# WeatherStation.net
KiCad netlist of a schematic drawn in EAGLE
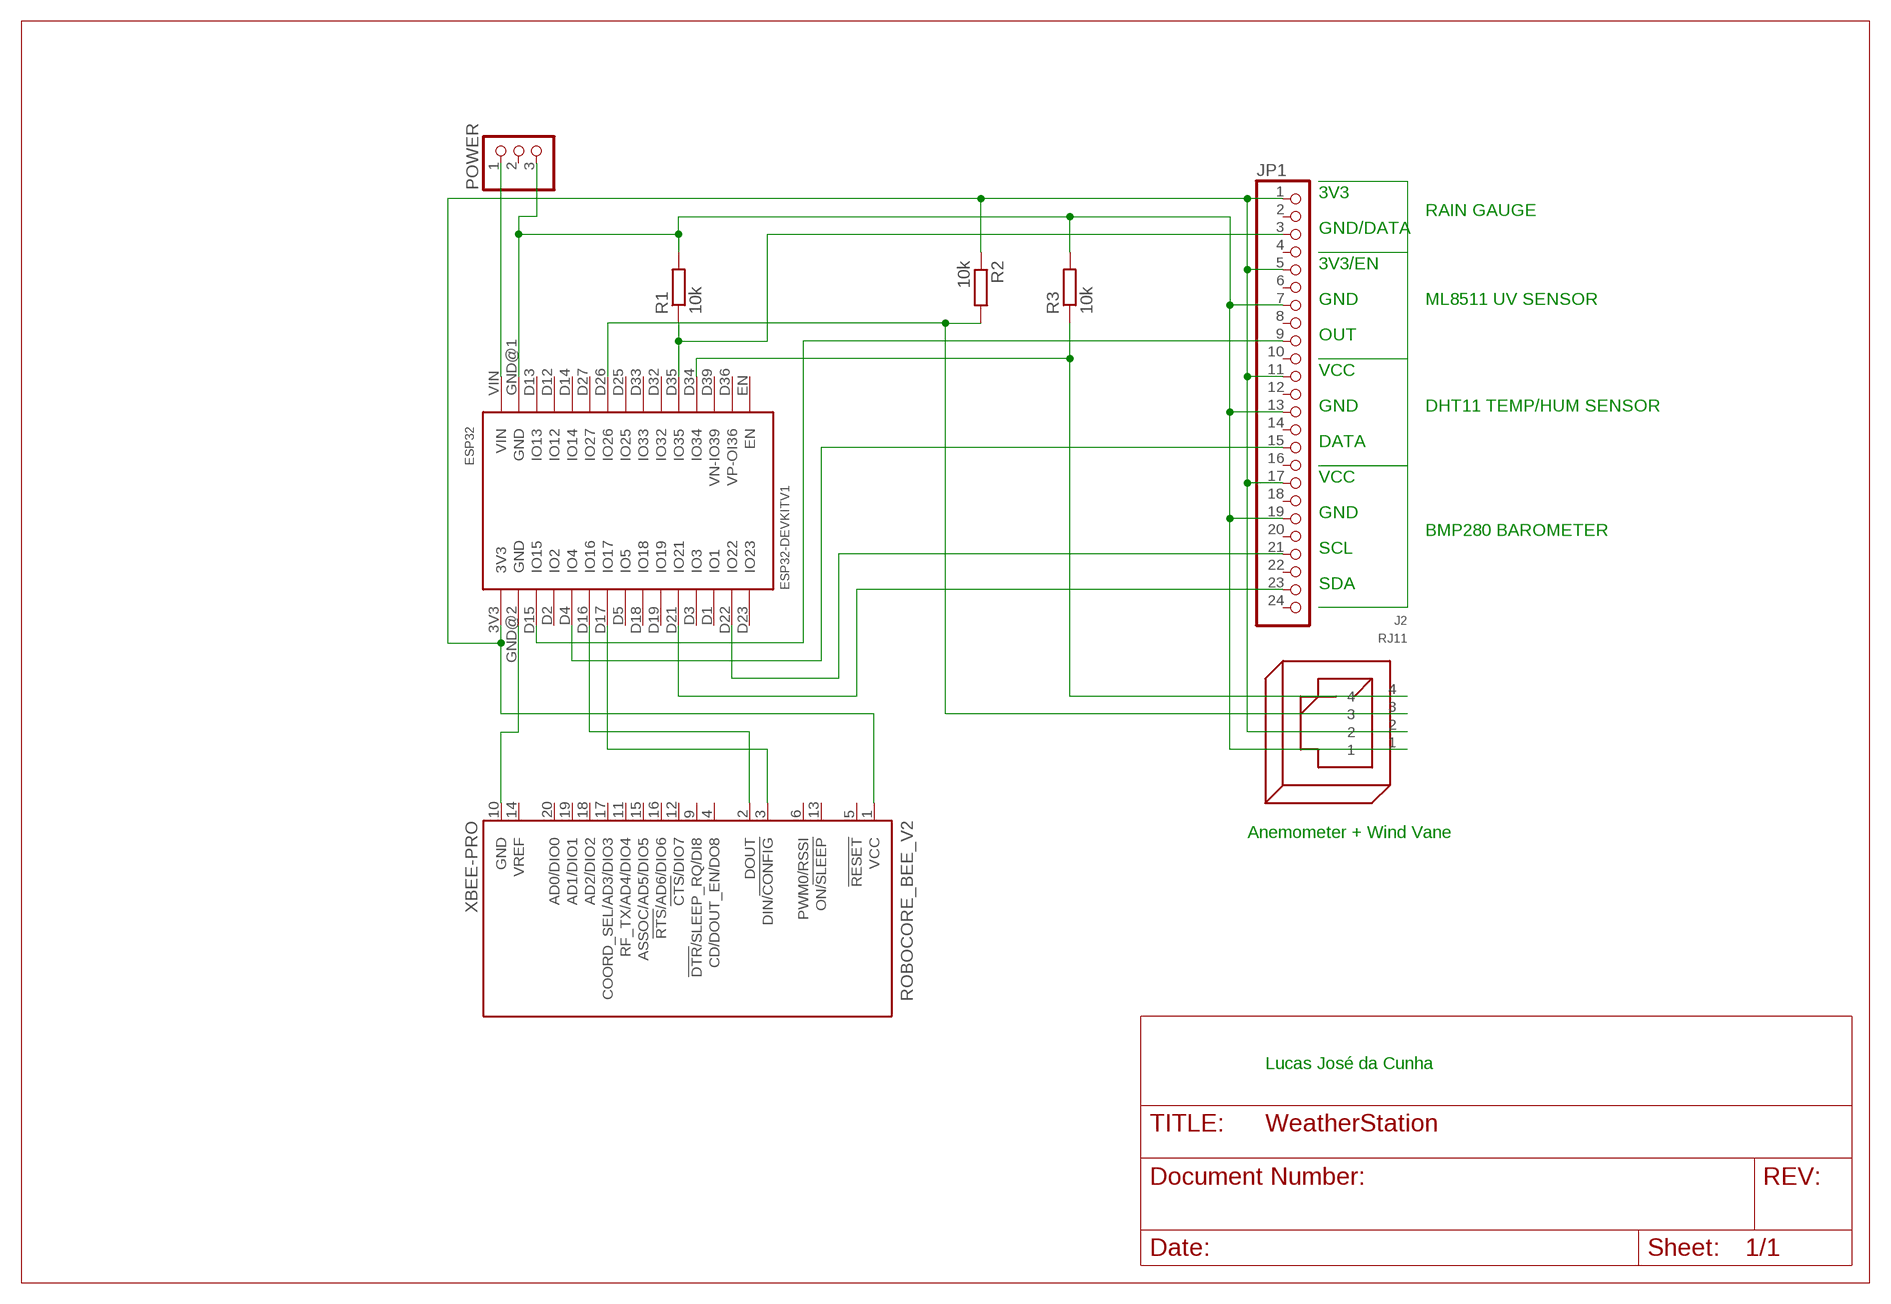
[diagram p0: schematic, sheet 1]

(export (version "E")
  (design (tool "Eeschema 10.0.6"))
  (components
    (comp (ref "ESP32")
      (value "ESP32DEVKITV1")
      (footprint "eagle-import:ESP32-DEVKITV1")
      (libsource (lib "eagle-import") (part "ESP32DEVKITV1"))
    )
    (comp (ref "J2")
      (value "RJ11")
      (footprint "eagle-import:RJ11")
      (libsource (lib "eagle-import") (part "RJ11"))
    )
    (comp (ref "JP1")
      (value "PINHD-1X24")
      (footprint "eagle-import:1X24")
      (libsource (lib "eagle-import") (part "PINHD-1X24"))
    )
    (comp (ref "POWER")
      (value "PINHD-1X3")
      (footprint "eagle-import:1X03")
      (libsource (lib "eagle-import") (part "PINHD-1X3"))
    )
    (comp (ref "R1")
      (value "10k")
      (footprint "eagle-import:0204_7")
      (libsource (lib "eagle-import") (part "R-EU_0204/7"))
    )
    (comp (ref "R2")
      (value "10k")
      (footprint "eagle-import:0204_7")
      (libsource (lib "eagle-import") (part "R-EU_0204/7"))
    )
    (comp (ref "R3")
      (value "10k")
      (footprint "eagle-import:0204_7")
      (libsource (lib "eagle-import") (part "R-EU_0204/7"))
    )
    (comp (ref "ROBOCORE_BEE_V2")
      (value "XBEE-PRO")
      (footprint "eagle-import:XBEE-PRO")
      (fields (field (name "MPN") "XBP24-AWI-001"))
      (libsource (lib "eagle-import") (part "XBEE-PRO"))
    )
  )
  (nets
    (net (code "1") (name "Net-(ESP32-GND-PadGND@1)") (class "Default")
      (node (ref "ESP32") (pin "GND@1") (pinfunction "GND_GND@1") (pintype "bidirectional"))
      (node (ref "J2") (pin "1") (pinfunction "1_1") (pintype "bidirectional"))
      (node (ref "JP1") (pin "13") (pinfunction "13_13") (pintype "passive"))
      (node (ref "JP1") (pin "19") (pinfunction "19_19") (pintype "passive"))
      (node (ref "JP1") (pin "7") (pinfunction "7_7") (pintype "passive"))
      (node (ref "POWER") (pin "3") (pinfunction "3_3") (pintype "passive"))
      (node (ref "R1") (pin "2") (pinfunction "2_2") (pintype "passive"))
      (node (ref "R3") (pin "2") (pinfunction "2_2") (pintype "passive"))
    )
    (net (code "2") (name "Net-(ESP32-IO4)") (class "Default")
      (node (ref "ESP32") (pin "D4") (pinfunction "IO4_D4") (pintype "bidirectional"))
      (node (ref "JP1") (pin "15") (pinfunction "15_15") (pintype "passive"))
    )
    (net (code "3") (name "Net-(ESP32-IO15)") (class "Default")
      (node (ref "ESP32") (pin "D15") (pinfunction "IO15_D15") (pintype "bidirectional"))
      (node (ref "JP1") (pin "9") (pinfunction "9_9") (pintype "passive"))
    )
    (net (code "4") (name "Net-(ESP32-IO16)") (class "Default")
      (node (ref "ESP32") (pin "D16") (pinfunction "IO16_D16") (pintype "bidirectional"))
      (node (ref "ROBOCORE_BEE_V2") (pin "2") (pinfunction "DOUT_2") (pintype "output"))
    )
    (net (code "5") (name "Net-(ESP32-IO17)") (class "Default")
      (node (ref "ESP32") (pin "D17") (pinfunction "IO17_D17") (pintype "bidirectional"))
      (node (ref "ROBOCORE_BEE_V2") (pin "3") (pinfunction "DIN/~{CONFIG}_3") (pintype "input"))
    )
    (net (code "6") (name "Net-(ESP32-IO21)") (class "Default")
      (node (ref "ESP32") (pin "D21") (pinfunction "IO21_D21") (pintype "bidirectional"))
      (node (ref "JP1") (pin "23") (pinfunction "23_23") (pintype "passive"))
    )
    (net (code "7") (name "Net-(ESP32-IO22)") (class "Default")
      (node (ref "ESP32") (pin "D22") (pinfunction "IO22_D22") (pintype "bidirectional"))
      (node (ref "JP1") (pin "21") (pinfunction "21_21") (pintype "passive"))
    )
    (net (code "8") (name "Net-(ESP32-IO26)") (class "Default")
      (node (ref "ESP32") (pin "D26") (pinfunction "IO26_D26") (pintype "bidirectional"))
      (node (ref "J2") (pin "3") (pinfunction "3_3") (pintype "bidirectional"))
      (node (ref "R2") (pin "2") (pinfunction "2_2") (pintype "passive"))
    )
    (net (code "9") (name "Net-(ESP32-IO34)") (class "Default")
      (node (ref "ESP32") (pin "D34") (pinfunction "IO34_D34") (pintype "bidirectional"))
      (node (ref "J2") (pin "4") (pinfunction "4_4") (pintype "bidirectional"))
      (node (ref "R3") (pin "1") (pinfunction "1_1") (pintype "passive"))
    )
    (net (code "10") (name "Net-(ESP32-IO35)") (class "Default")
      (node (ref "ESP32") (pin "D35") (pinfunction "IO35_D35") (pintype "bidirectional"))
      (node (ref "JP1") (pin "3") (pinfunction "3_3") (pintype "passive"))
      (node (ref "R1") (pin "1") (pinfunction "1_1") (pintype "passive"))
    )
    (net (code "11") (name "Net-(ESP32-PadVIN)") (class "Default")
      (node (ref "ESP32") (pin "VIN") (pinfunction "VIN_VIN") (pintype "bidirectional"))
      (node (ref "POWER") (pin "1") (pinfunction "1_1") (pintype "passive"))
    )
    (net (code "12") (name "Net-(ROBOCORE_BEE_V2-GND)") (class "Default")
      (node (ref "ESP32") (pin "GND@2") (pinfunction "GND_GND@2") (pintype "bidirectional"))
      (node (ref "ROBOCORE_BEE_V2") (pin "10") (pinfunction "GND_10") (pintype "power_in"))
    )
    (net (code "13") (name "Net-(ROBOCORE_BEE_V2-VCC)") (class "Default")
      (node (ref "ESP32") (pin "3V3") (pinfunction "3V3_3V3") (pintype "bidirectional"))
      (node (ref "J2") (pin "2") (pinfunction "2_2") (pintype "bidirectional"))
      (node (ref "JP1") (pin "1") (pinfunction "1_1") (pintype "passive"))
      (node (ref "JP1") (pin "11") (pinfunction "11_11") (pintype "passive"))
      (node (ref "JP1") (pin "17") (pinfunction "17_17") (pintype "passive"))
      (node (ref "JP1") (pin "5") (pinfunction "5_5") (pintype "passive"))
      (node (ref "R2") (pin "1") (pinfunction "1_1") (pintype "passive"))
      (node (ref "ROBOCORE_BEE_V2") (pin "1") (pinfunction "VCC_1") (pintype "power_in"))
    )
    (net (code "14") (name "unconnected-(ESP32-IO1-PadD1)") (class "Default")
      (node (ref "ESP32") (pin "D1") (pinfunction "IO1_D1") (pintype "bidirectional"))
    )
    (net (code "15") (name "unconnected-(ESP32-IO2-PadD2)") (class "Default")
      (node (ref "ESP32") (pin "D2") (pinfunction "IO2_D2") (pintype "bidirectional"))
    )
    (net (code "16") (name "unconnected-(ESP32-IO3-PadD3)") (class "Default")
      (node (ref "ESP32") (pin "D3") (pinfunction "IO3_D3") (pintype "bidirectional"))
    )
    (net (code "17") (name "unconnected-(ESP32-IO5-PadD5)") (class "Default")
      (node (ref "ESP32") (pin "D5") (pinfunction "IO5_D5") (pintype "bidirectional"))
    )
    (net (code "18") (name "unconnected-(ESP32-IO12-PadD12)") (class "Default")
      (node (ref "ESP32") (pin "D12") (pinfunction "IO12_D12") (pintype "bidirectional"))
    )
    (net (code "19") (name "unconnected-(ESP32-IO13-PadD13)") (class "Default")
      (node (ref "ESP32") (pin "D13") (pinfunction "IO13_D13") (pintype "bidirectional"))
    )
    (net (code "20") (name "unconnected-(ESP32-IO14-PadD14)") (class "Default")
      (node (ref "ESP32") (pin "D14") (pinfunction "IO14_D14") (pintype "bidirectional"))
    )
    (net (code "21") (name "unconnected-(ESP32-IO18-PadD18)") (class "Default")
      (node (ref "ESP32") (pin "D18") (pinfunction "IO18_D18") (pintype "bidirectional"))
    )
    (net (code "22") (name "unconnected-(ESP32-IO19-PadD19)") (class "Default")
      (node (ref "ESP32") (pin "D19") (pinfunction "IO19_D19") (pintype "bidirectional"))
    )
    (net (code "23") (name "unconnected-(ESP32-IO23-PadD23)") (class "Default")
      (node (ref "ESP32") (pin "D23") (pinfunction "IO23_D23") (pintype "bidirectional"))
    )
    (net (code "24") (name "unconnected-(ESP32-IO25-PadD25)") (class "Default")
      (node (ref "ESP32") (pin "D25") (pinfunction "IO25_D25") (pintype "bidirectional"))
    )
    (net (code "25") (name "unconnected-(ESP32-IO27-PadD27)") (class "Default")
      (node (ref "ESP32") (pin "D27") (pinfunction "IO27_D27") (pintype "bidirectional"))
    )
    (net (code "26") (name "unconnected-(ESP32-IO32-PadD32)") (class "Default")
      (node (ref "ESP32") (pin "D32") (pinfunction "IO32_D32") (pintype "bidirectional"))
    )
    (net (code "27") (name "unconnected-(ESP32-IO33-PadD33)") (class "Default")
      (node (ref "ESP32") (pin "D33") (pinfunction "IO33_D33") (pintype "bidirectional"))
    )
    (net (code "28") (name "unconnected-(ESP32-PadEN)") (class "Default")
      (node (ref "ESP32") (pin "EN") (pinfunction "EN_EN") (pintype "bidirectional"))
    )
    (net (code "29") (name "unconnected-(ESP32-VN-IO39-PadD39)") (class "Default")
      (node (ref "ESP32") (pin "D39") (pinfunction "VN-IO39_D39") (pintype "bidirectional"))
    )
    (net (code "30") (name "unconnected-(ESP32-VP-OI36-PadD36)") (class "Default")
      (node (ref "ESP32") (pin "D36") (pinfunction "VP-OI36_D36") (pintype "bidirectional"))
    )
    (net (code "31") (name "unconnected-(JP1-Pad2)") (class "Default")
      (node (ref "JP1") (pin "2") (pinfunction "2_2") (pintype "passive"))
    )
    (net (code "32") (name "unconnected-(JP1-Pad4)") (class "Default")
      (node (ref "JP1") (pin "4") (pinfunction "4_4") (pintype "passive"))
    )
    (net (code "33") (name "unconnected-(JP1-Pad6)") (class "Default")
      (node (ref "JP1") (pin "6") (pinfunction "6_6") (pintype "passive"))
    )
    (net (code "34") (name "unconnected-(JP1-Pad8)") (class "Default")
      (node (ref "JP1") (pin "8") (pinfunction "8_8") (pintype "passive"))
    )
    (net (code "35") (name "unconnected-(JP1-Pad10)") (class "Default")
      (node (ref "JP1") (pin "10") (pinfunction "10_10") (pintype "passive"))
    )
    (net (code "36") (name "unconnected-(JP1-Pad12)") (class "Default")
      (node (ref "JP1") (pin "12") (pinfunction "12_12") (pintype "passive"))
    )
    (net (code "37") (name "unconnected-(JP1-Pad14)") (class "Default")
      (node (ref "JP1") (pin "14") (pinfunction "14_14") (pintype "passive"))
    )
    (net (code "38") (name "unconnected-(JP1-Pad16)") (class "Default")
      (node (ref "JP1") (pin "16") (pinfunction "16_16") (pintype "passive"))
    )
    (net (code "39") (name "unconnected-(JP1-Pad18)") (class "Default")
      (node (ref "JP1") (pin "18") (pinfunction "18_18") (pintype "passive"))
    )
    (net (code "40") (name "unconnected-(JP1-Pad20)") (class "Default")
      (node (ref "JP1") (pin "20") (pinfunction "20_20") (pintype "passive"))
    )
    (net (code "41") (name "unconnected-(JP1-Pad22)") (class "Default")
      (node (ref "JP1") (pin "22") (pinfunction "22_22") (pintype "passive"))
    )
    (net (code "42") (name "unconnected-(JP1-Pad24)") (class "Default")
      (node (ref "JP1") (pin "24") (pinfunction "24_24") (pintype "passive"))
    )
    (net (code "43") (name "unconnected-(POWER-Pad2)") (class "Default")
      (node (ref "POWER") (pin "2") (pinfunction "2_2") (pintype "passive"))
    )
    (net (code "44") (name "unconnected-(ROBOCORE_BEE_V2-AD0{slash}DIO0-Pad20)") (class "Default")
      (node (ref "ROBOCORE_BEE_V2") (pin "20") (pinfunction "AD0/DIO0_20") (pintype "bidirectional"))
    )
    (net (code "45") (name "unconnected-(ROBOCORE_BEE_V2-AD1{slash}DIO1-Pad19)") (class "Default")
      (node (ref "ROBOCORE_BEE_V2") (pin "19") (pinfunction "AD1/DIO1_19") (pintype "bidirectional"))
    )
    (net (code "46") (name "unconnected-(ROBOCORE_BEE_V2-AD2{slash}DIO2-Pad18)") (class "Default")
      (node (ref "ROBOCORE_BEE_V2") (pin "18") (pinfunction "AD2/DIO2_18") (pintype "bidirectional"))
    )
    (net (code "47") (name "unconnected-(ROBOCORE_BEE_V2-ASSOC{slash}AD5{slash}DIO5-Pad15)") (class "Default")
      (node (ref "ROBOCORE_BEE_V2") (pin "15") (pinfunction "ASSOC/AD5/DIO5_15") (pintype "bidirectional"))
    )
    (net (code "48") (name "unconnected-(ROBOCORE_BEE_V2-CD{slash}DOUT_EN{slash}DO8-Pad4)") (class "Default")
      (node (ref "ROBOCORE_BEE_V2") (pin "4") (pinfunction "CD/DOUT_EN/DO8_4") (pintype "output"))
    )
    (net (code "49") (name "unconnected-(ROBOCORE_BEE_V2-COORD_SEL{slash}AD3{slash}DIO3-Pad17)") (class "Default")
      (node (ref "ROBOCORE_BEE_V2") (pin "17") (pinfunction "COORD_SEL/AD3/DIO3_17") (pintype "bidirectional"))
    )
    (net (code "50") (name "unconnected-(ROBOCORE_BEE_V2-ON{slash}~{SLEEP}-Pad13)") (class "Default")
      (node (ref "ROBOCORE_BEE_V2") (pin "13") (pinfunction "ON/~{SLEEP}_13") (pintype "output"))
    )
    (net (code "51") (name "unconnected-(ROBOCORE_BEE_V2-PWM0{slash}RSSI-Pad6)") (class "Default")
      (node (ref "ROBOCORE_BEE_V2") (pin "6") (pinfunction "PWM0/RSSI_6") (pintype "output"))
    )
    (net (code "52") (name "unconnected-(ROBOCORE_BEE_V2-RF_TX{slash}AD4{slash}DIO4-Pad11)") (class "Default")
      (node (ref "ROBOCORE_BEE_V2") (pin "11") (pinfunction "RF_TX/AD4/DIO4_11") (pintype "bidirectional"))
    )
    (net (code "53") (name "unconnected-(ROBOCORE_BEE_V2-VREF-Pad14)") (class "Default")
      (node (ref "ROBOCORE_BEE_V2") (pin "14") (pinfunction "VREF_14") (pintype "input"))
    )
    (net (code "54") (name "unconnected-(ROBOCORE_BEE_V2-~{CTS}{slash}DIO7-Pad12)") (class "Default")
      (node (ref "ROBOCORE_BEE_V2") (pin "12") (pinfunction "~{CTS}/DIO7_12") (pintype "bidirectional"))
    )
    (net (code "55") (name "unconnected-(ROBOCORE_BEE_V2-~{DTR}{slash}SLEEP_RQ{slash}DI8-Pad9)") (class "Default")
      (node (ref "ROBOCORE_BEE_V2") (pin "9") (pinfunction "~{DTR}/SLEEP_RQ/DI8_9") (pintype "bidirectional"))
    )
    (net (code "56") (name "unconnected-(ROBOCORE_BEE_V2-~{RESET}-Pad5)") (class "Default")
      (node (ref "ROBOCORE_BEE_V2") (pin "5") (pinfunction "~{RESET}_5") (pintype "input"))
    )
    (net (code "57") (name "unconnected-(ROBOCORE_BEE_V2-~{RTS}{slash}AD6{slash}DIO6-Pad16)") (class "Default")
      (node (ref "ROBOCORE_BEE_V2") (pin "16") (pinfunction "~{RTS}/AD6/DIO6_16") (pintype "bidirectional"))
    )
  )
)
